# NPNTransistorArray.net
KiCad netlist of a schematic drawn in Altium Designer
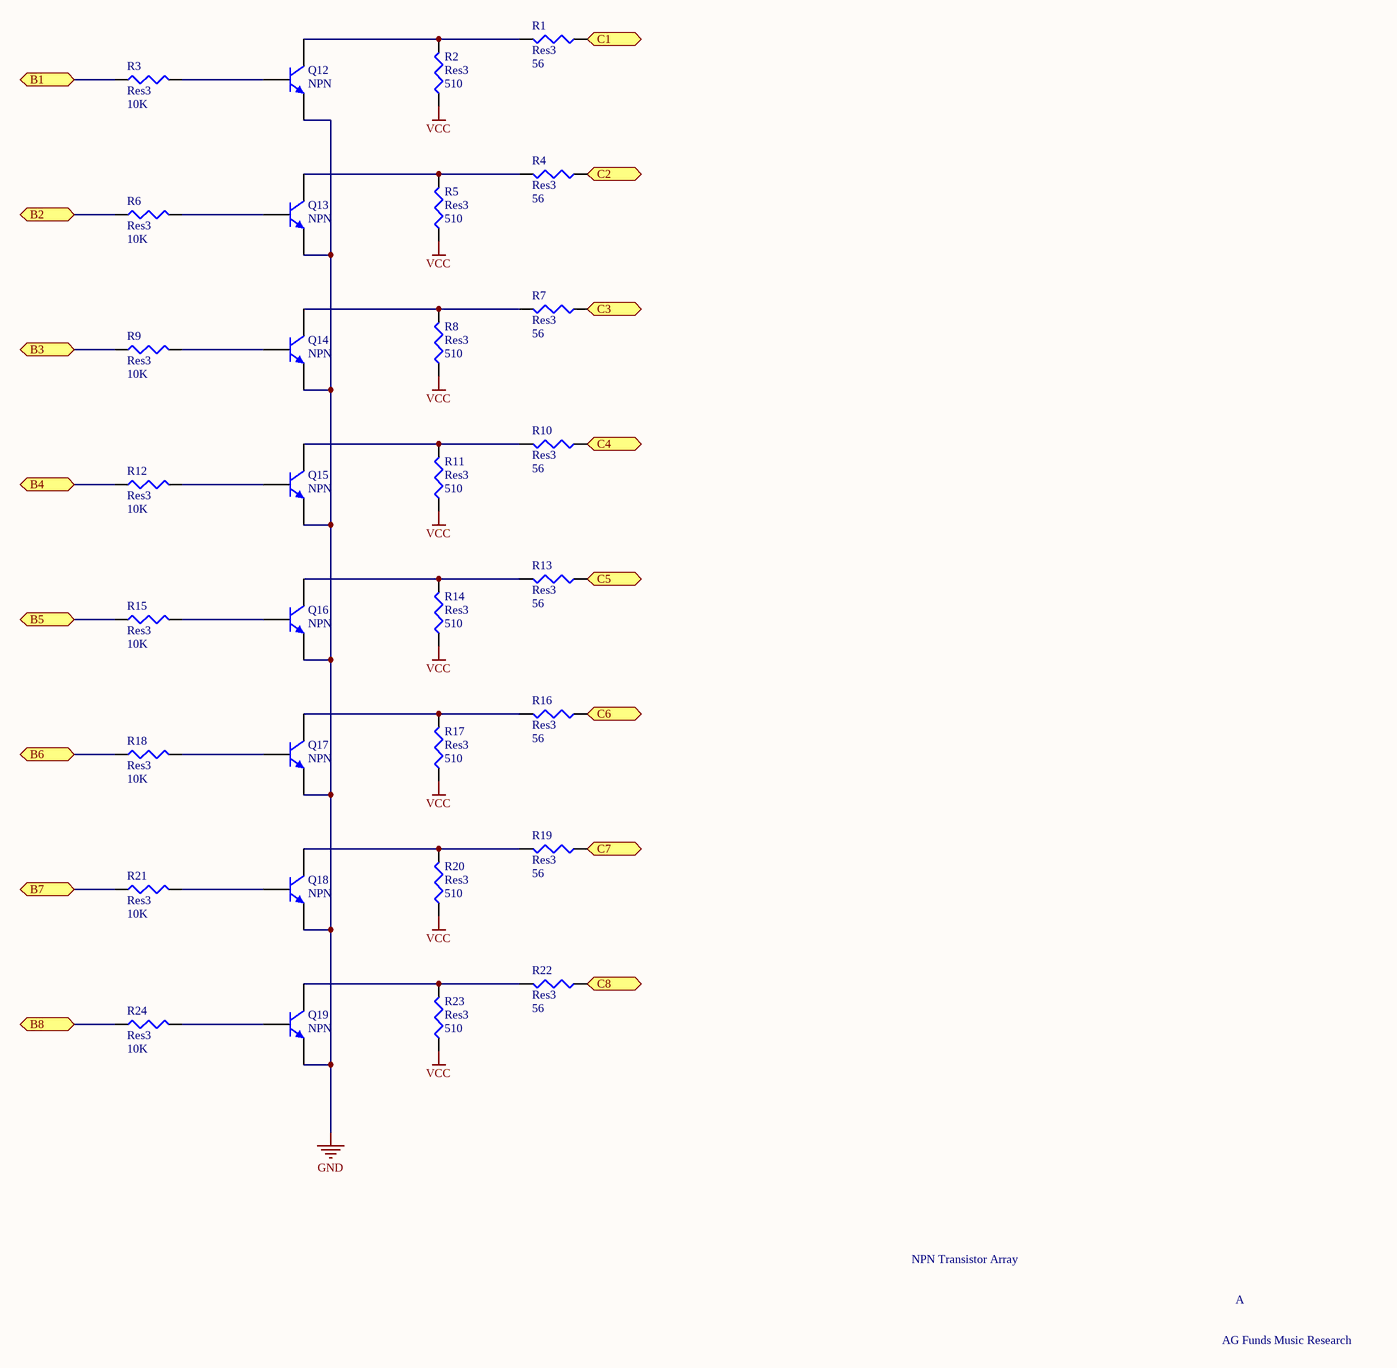
[diagram p0: NPNTransistorArray.SchDoc]

(export (version "E")
  (design (tool "Eeschema 10.0.6"))
  (components
    (comp (ref "Q12")
      (value "NPN")
      (footprint "SOT95P230-3N")
      (description "BC817/BC818 SMD NPN Bipolar Transistor")
      (fields (field (name "PUBLISHER") "Altium Limited"))
      (libsource (lib "MIDIPiano_7") (part "NPN"))
    )
    (comp (ref "Q13")
      (value "NPN")
      (footprint "SOT95P230-3N")
      (description "BC817/BC818 SMD NPN Bipolar Transistor")
      (fields (field (name "PUBLISHER") "Altium Limited"))
      (libsource (lib "MIDIPiano_7") (part "NPN"))
    )
    (comp (ref "Q14")
      (value "NPN")
      (footprint "SOT95P230-3N")
      (description "BC817/BC818 SMD NPN Bipolar Transistor")
      (fields (field (name "PUBLISHER") "Altium Limited"))
      (libsource (lib "MIDIPiano_7") (part "NPN"))
    )
    (comp (ref "Q15")
      (value "NPN")
      (footprint "SOT95P230-3N")
      (description "BC817/BC818 SMD NPN Bipolar Transistor")
      (fields (field (name "PUBLISHER") "Altium Limited"))
      (libsource (lib "MIDIPiano_7") (part "NPN"))
    )
    (comp (ref "Q16")
      (value "NPN")
      (footprint "SOT95P230-3N")
      (description "BC817/BC818 SMD NPN Bipolar Transistor")
      (fields (field (name "PUBLISHER") "Altium Limited"))
      (libsource (lib "MIDIPiano_7") (part "NPN"))
    )
    (comp (ref "Q17")
      (value "NPN")
      (footprint "SOT95P230-3N")
      (description "BC817/BC818 SMD NPN Bipolar Transistor")
      (fields (field (name "PUBLISHER") "Altium Limited"))
      (libsource (lib "MIDIPiano_7") (part "NPN"))
    )
    (comp (ref "Q18")
      (value "NPN")
      (footprint "SOT95P230-3N")
      (description "BC817/BC818 SMD NPN Bipolar Transistor")
      (fields (field (name "PUBLISHER") "Altium Limited"))
      (libsource (lib "MIDIPiano_7") (part "NPN"))
    )
    (comp (ref "Q19")
      (value "NPN")
      (footprint "SOT95P230-3N")
      (description "BC817/BC818 SMD NPN Bipolar Transistor")
      (fields (field (name "PUBLISHER") "Altium Limited"))
      (libsource (lib "MIDIPiano_7") (part "NPN"))
    )
    (comp (ref "R1")
      (value "Res3")
      (footprint "J1-0603")
      (description "Resistor")
      (fields (field (name "ALTIUM_VALUE") "56") (field (name "PUBLISHER") "Altium Limited"))
      (libsource (lib "MIDIPiano") (part "Res3"))
    )
    (comp (ref "R2")
      (value "Res3")
      (footprint "J1-0603")
      (description "Resistor")
      (fields (field (name "ALTIUM_VALUE") "510") (field (name "PUBLISHER") "Altium Limited"))
      (libsource (lib "MIDIPiano") (part "Res3"))
    )
    (comp (ref "R3")
      (value "Res3")
      (footprint "J1-0603")
      (description "Resistor")
      (fields (field (name "ALTIUM_VALUE") "10K") (field (name "PUBLISHER") "Altium Limited"))
      (libsource (lib "MIDIPiano") (part "Res3"))
    )
    (comp (ref "R4")
      (value "Res3")
      (footprint "J1-0603")
      (description "Resistor")
      (fields (field (name "ALTIUM_VALUE") "56") (field (name "PUBLISHER") "Altium Limited"))
      (libsource (lib "MIDIPiano") (part "Res3"))
    )
    (comp (ref "R5")
      (value "Res3")
      (footprint "J1-0603")
      (description "Resistor")
      (fields (field (name "ALTIUM_VALUE") "510") (field (name "PUBLISHER") "Altium Limited"))
      (libsource (lib "MIDIPiano") (part "Res3"))
    )
    (comp (ref "R6")
      (value "Res3")
      (footprint "J1-0603")
      (description "Resistor")
      (fields (field (name "ALTIUM_VALUE") "10K") (field (name "PUBLISHER") "Altium Limited"))
      (libsource (lib "MIDIPiano") (part "Res3"))
    )
    (comp (ref "R7")
      (value "Res3")
      (footprint "J1-0603")
      (description "Resistor")
      (fields (field (name "ALTIUM_VALUE") "56") (field (name "PUBLISHER") "Altium Limited"))
      (libsource (lib "MIDIPiano") (part "Res3"))
    )
    (comp (ref "R8")
      (value "Res3")
      (footprint "J1-0603")
      (description "Resistor")
      (fields (field (name "ALTIUM_VALUE") "510") (field (name "PUBLISHER") "Altium Limited"))
      (libsource (lib "MIDIPiano") (part "Res3"))
    )
    (comp (ref "R9")
      (value "Res3")
      (footprint "J1-0603")
      (description "Resistor")
      (fields (field (name "ALTIUM_VALUE") "10K") (field (name "PUBLISHER") "Altium Limited"))
      (libsource (lib "MIDIPiano") (part "Res3"))
    )
    (comp (ref "R10")
      (value "Res3")
      (footprint "J1-0603")
      (description "Resistor")
      (fields (field (name "ALTIUM_VALUE") "56") (field (name "PUBLISHER") "Altium Limited"))
      (libsource (lib "MIDIPiano") (part "Res3"))
    )
    (comp (ref "R11")
      (value "Res3")
      (footprint "J1-0603")
      (description "Resistor")
      (fields (field (name "ALTIUM_VALUE") "510") (field (name "PUBLISHER") "Altium Limited"))
      (libsource (lib "MIDIPiano") (part "Res3"))
    )
    (comp (ref "R12")
      (value "Res3")
      (footprint "J1-0603")
      (description "Resistor")
      (fields (field (name "ALTIUM_VALUE") "10K") (field (name "PUBLISHER") "Altium Limited"))
      (libsource (lib "MIDIPiano") (part "Res3"))
    )
    (comp (ref "R13")
      (value "Res3")
      (footprint "J1-0603")
      (description "Resistor")
      (fields (field (name "ALTIUM_VALUE") "56") (field (name "PUBLISHER") "Altium Limited"))
      (libsource (lib "MIDIPiano") (part "Res3"))
    )
    (comp (ref "R14")
      (value "Res3")
      (footprint "J1-0603")
      (description "Resistor")
      (fields (field (name "ALTIUM_VALUE") "510") (field (name "PUBLISHER") "Altium Limited"))
      (libsource (lib "MIDIPiano") (part "Res3"))
    )
    (comp (ref "R15")
      (value "Res3")
      (footprint "J1-0603")
      (description "Resistor")
      (fields (field (name "ALTIUM_VALUE") "10K") (field (name "PUBLISHER") "Altium Limited"))
      (libsource (lib "MIDIPiano") (part "Res3"))
    )
    (comp (ref "R16")
      (value "Res3")
      (footprint "J1-0603")
      (description "Resistor")
      (fields (field (name "ALTIUM_VALUE") "56") (field (name "PUBLISHER") "Altium Limited"))
      (libsource (lib "MIDIPiano") (part "Res3"))
    )
    (comp (ref "R17")
      (value "Res3")
      (footprint "J1-0603")
      (description "Resistor")
      (fields (field (name "ALTIUM_VALUE") "510") (field (name "PUBLISHER") "Altium Limited"))
      (libsource (lib "MIDIPiano") (part "Res3"))
    )
    (comp (ref "R18")
      (value "Res3")
      (footprint "J1-0603")
      (description "Resistor")
      (fields (field (name "ALTIUM_VALUE") "10K") (field (name "PUBLISHER") "Altium Limited"))
      (libsource (lib "MIDIPiano") (part "Res3"))
    )
    (comp (ref "R19")
      (value "Res3")
      (footprint "J1-0603")
      (description "Resistor")
      (fields (field (name "ALTIUM_VALUE") "56") (field (name "PUBLISHER") "Altium Limited"))
      (libsource (lib "MIDIPiano") (part "Res3"))
    )
    (comp (ref "R20")
      (value "Res3")
      (footprint "J1-0603")
      (description "Resistor")
      (fields (field (name "ALTIUM_VALUE") "510") (field (name "PUBLISHER") "Altium Limited"))
      (libsource (lib "MIDIPiano") (part "Res3"))
    )
    (comp (ref "R21")
      (value "Res3")
      (footprint "J1-0603")
      (description "Resistor")
      (fields (field (name "ALTIUM_VALUE") "10K") (field (name "PUBLISHER") "Altium Limited"))
      (libsource (lib "MIDIPiano") (part "Res3"))
    )
    (comp (ref "R22")
      (value "Res3")
      (footprint "J1-0603")
      (description "Resistor")
      (fields (field (name "ALTIUM_VALUE") "56") (field (name "PUBLISHER") "Altium Limited"))
      (libsource (lib "MIDIPiano") (part "Res3"))
    )
    (comp (ref "R23")
      (value "Res3")
      (footprint "J1-0603")
      (description "Resistor")
      (fields (field (name "ALTIUM_VALUE") "510") (field (name "PUBLISHER") "Altium Limited"))
      (libsource (lib "MIDIPiano") (part "Res3"))
    )
    (comp (ref "R24")
      (value "Res3")
      (footprint "J1-0603")
      (description "Resistor")
      (fields (field (name "ALTIUM_VALUE") "10K") (field (name "PUBLISHER") "Altium Limited"))
      (libsource (lib "MIDIPiano") (part "Res3"))
    )
  )
  (nets
    (net (code "1") (name "/B1") (class "Default")
      (node (ref "R3") (pin "1") (pinfunction "1_1") (pintype "passive"))
    )
    (net (code "2") (name "/B2") (class "Default")
      (node (ref "R6") (pin "1") (pinfunction "1_1") (pintype "passive"))
    )
    (net (code "3") (name "/B3") (class "Default")
      (node (ref "R9") (pin "1") (pinfunction "1_1") (pintype "passive"))
    )
    (net (code "4") (name "/B4") (class "Default")
      (node (ref "R12") (pin "1") (pinfunction "1_1") (pintype "passive"))
    )
    (net (code "5") (name "/B5") (class "Default")
      (node (ref "R15") (pin "1") (pinfunction "1_1") (pintype "passive"))
    )
    (net (code "6") (name "/B6") (class "Default")
      (node (ref "R18") (pin "1") (pinfunction "1_1") (pintype "passive"))
    )
    (net (code "7") (name "/B7") (class "Default")
      (node (ref "R21") (pin "1") (pinfunction "1_1") (pintype "passive"))
    )
    (net (code "8") (name "/B8") (class "Default")
      (node (ref "R24") (pin "1") (pinfunction "1_1") (pintype "passive"))
    )
    (net (code "9") (name "/C1") (class "Default")
      (node (ref "R1") (pin "1") (pinfunction "1_1") (pintype "passive"))
    )
    (net (code "10") (name "/C2") (class "Default")
      (node (ref "R4") (pin "1") (pinfunction "1_1") (pintype "passive"))
    )
    (net (code "11") (name "/C3") (class "Default")
      (node (ref "R7") (pin "1") (pinfunction "1_1") (pintype "passive"))
    )
    (net (code "12") (name "/C4") (class "Default")
      (node (ref "R10") (pin "1") (pinfunction "1_1") (pintype "passive"))
    )
    (net (code "13") (name "/C5") (class "Default")
      (node (ref "R13") (pin "1") (pinfunction "1_1") (pintype "passive"))
    )
    (net (code "14") (name "/C6") (class "Default")
      (node (ref "R16") (pin "1") (pinfunction "1_1") (pintype "passive"))
    )
    (net (code "15") (name "/C7") (class "Default")
      (node (ref "R19") (pin "1") (pinfunction "1_1") (pintype "passive"))
    )
    (net (code "16") (name "/C8") (class "Default")
      (node (ref "R22") (pin "1") (pinfunction "1_1") (pintype "passive"))
    )
    (net (code "17") (name "GND") (class "Default")
      (node (ref "Q12") (pin "3") (pinfunction "E_3") (pintype "passive"))
      (node (ref "Q13") (pin "3") (pinfunction "E_3") (pintype "passive"))
      (node (ref "Q14") (pin "3") (pinfunction "E_3") (pintype "passive"))
      (node (ref "Q15") (pin "3") (pinfunction "E_3") (pintype "passive"))
      (node (ref "Q16") (pin "3") (pinfunction "E_3") (pintype "passive"))
      (node (ref "Q17") (pin "3") (pinfunction "E_3") (pintype "passive"))
      (node (ref "Q18") (pin "3") (pinfunction "E_3") (pintype "passive"))
      (node (ref "Q19") (pin "3") (pinfunction "E_3") (pintype "passive"))
    )
    (net (code "18") (name "Net-(Q12-B)") (class "Default")
      (node (ref "Q12") (pin "2") (pinfunction "B_2") (pintype "passive"))
      (node (ref "R3") (pin "2") (pinfunction "2_2") (pintype "passive"))
    )
    (net (code "19") (name "Net-(Q12-C)") (class "Default")
      (node (ref "Q12") (pin "1") (pinfunction "C_1") (pintype "passive"))
      (node (ref "R1") (pin "2") (pinfunction "2_2") (pintype "passive"))
      (node (ref "R2") (pin "2") (pinfunction "2_2") (pintype "passive"))
    )
    (net (code "20") (name "Net-(Q13-B)") (class "Default")
      (node (ref "Q13") (pin "2") (pinfunction "B_2") (pintype "passive"))
      (node (ref "R6") (pin "2") (pinfunction "2_2") (pintype "passive"))
    )
    (net (code "21") (name "Net-(Q13-C)") (class "Default")
      (node (ref "Q13") (pin "1") (pinfunction "C_1") (pintype "passive"))
      (node (ref "R4") (pin "2") (pinfunction "2_2") (pintype "passive"))
      (node (ref "R5") (pin "2") (pinfunction "2_2") (pintype "passive"))
    )
    (net (code "22") (name "Net-(Q14-B)") (class "Default")
      (node (ref "Q14") (pin "2") (pinfunction "B_2") (pintype "passive"))
      (node (ref "R9") (pin "2") (pinfunction "2_2") (pintype "passive"))
    )
    (net (code "23") (name "Net-(Q14-C)") (class "Default")
      (node (ref "Q14") (pin "1") (pinfunction "C_1") (pintype "passive"))
      (node (ref "R7") (pin "2") (pinfunction "2_2") (pintype "passive"))
      (node (ref "R8") (pin "2") (pinfunction "2_2") (pintype "passive"))
    )
    (net (code "24") (name "Net-(Q15-B)") (class "Default")
      (node (ref "Q15") (pin "2") (pinfunction "B_2") (pintype "passive"))
      (node (ref "R12") (pin "2") (pinfunction "2_2") (pintype "passive"))
    )
    (net (code "25") (name "Net-(Q15-C)") (class "Default")
      (node (ref "Q15") (pin "1") (pinfunction "C_1") (pintype "passive"))
      (node (ref "R10") (pin "2") (pinfunction "2_2") (pintype "passive"))
      (node (ref "R11") (pin "2") (pinfunction "2_2") (pintype "passive"))
    )
    (net (code "26") (name "Net-(Q16-B)") (class "Default")
      (node (ref "Q16") (pin "2") (pinfunction "B_2") (pintype "passive"))
      (node (ref "R15") (pin "2") (pinfunction "2_2") (pintype "passive"))
    )
    (net (code "27") (name "Net-(Q16-C)") (class "Default")
      (node (ref "Q16") (pin "1") (pinfunction "C_1") (pintype "passive"))
      (node (ref "R13") (pin "2") (pinfunction "2_2") (pintype "passive"))
      (node (ref "R14") (pin "2") (pinfunction "2_2") (pintype "passive"))
    )
    (net (code "28") (name "Net-(Q17-B)") (class "Default")
      (node (ref "Q17") (pin "2") (pinfunction "B_2") (pintype "passive"))
      (node (ref "R18") (pin "2") (pinfunction "2_2") (pintype "passive"))
    )
    (net (code "29") (name "Net-(Q17-C)") (class "Default")
      (node (ref "Q17") (pin "1") (pinfunction "C_1") (pintype "passive"))
      (node (ref "R16") (pin "2") (pinfunction "2_2") (pintype "passive"))
      (node (ref "R17") (pin "2") (pinfunction "2_2") (pintype "passive"))
    )
    (net (code "30") (name "Net-(Q18-B)") (class "Default")
      (node (ref "Q18") (pin "2") (pinfunction "B_2") (pintype "passive"))
      (node (ref "R21") (pin "2") (pinfunction "2_2") (pintype "passive"))
    )
    (net (code "31") (name "Net-(Q18-C)") (class "Default")
      (node (ref "Q18") (pin "1") (pinfunction "C_1") (pintype "passive"))
      (node (ref "R19") (pin "2") (pinfunction "2_2") (pintype "passive"))
      (node (ref "R20") (pin "2") (pinfunction "2_2") (pintype "passive"))
    )
    (net (code "32") (name "Net-(Q19-B)") (class "Default")
      (node (ref "Q19") (pin "2") (pinfunction "B_2") (pintype "passive"))
      (node (ref "R24") (pin "2") (pinfunction "2_2") (pintype "passive"))
    )
    (net (code "33") (name "Net-(Q19-C)") (class "Default")
      (node (ref "Q19") (pin "1") (pinfunction "C_1") (pintype "passive"))
      (node (ref "R22") (pin "2") (pinfunction "2_2") (pintype "passive"))
      (node (ref "R23") (pin "2") (pinfunction "2_2") (pintype "passive"))
    )
    (net (code "34") (name "VCC") (class "Default")
      (node (ref "R11") (pin "1") (pinfunction "1_1") (pintype "passive"))
      (node (ref "R14") (pin "1") (pinfunction "1_1") (pintype "passive"))
      (node (ref "R17") (pin "1") (pinfunction "1_1") (pintype "passive"))
      (node (ref "R2") (pin "1") (pinfunction "1_1") (pintype "passive"))
      (node (ref "R20") (pin "1") (pinfunction "1_1") (pintype "passive"))
      (node (ref "R23") (pin "1") (pinfunction "1_1") (pintype "passive"))
      (node (ref "R5") (pin "1") (pinfunction "1_1") (pintype "passive"))
      (node (ref "R8") (pin "1") (pinfunction "1_1") (pintype "passive"))
    )
  )
)
